# crystals.net
KiCad netlist of a schematic drawn in Altium Designer
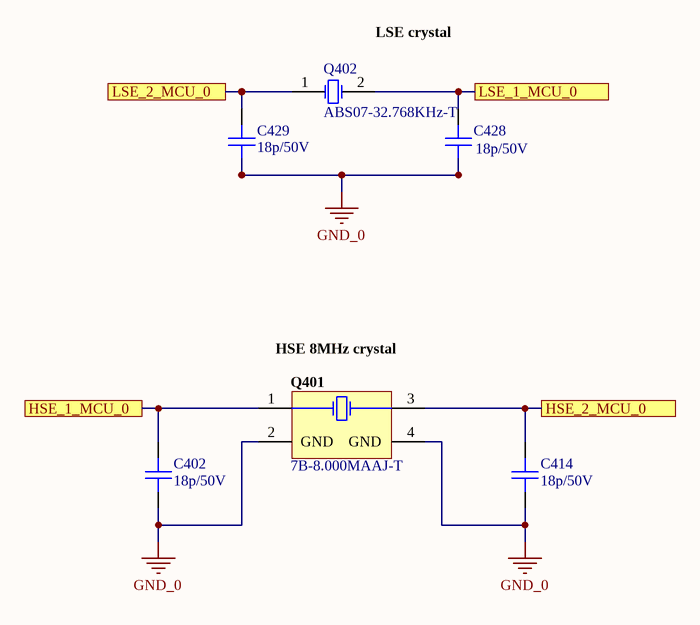
[diagram p0: crystals.SchDoc]

(export (version "E")
  (design (tool "Eeschema 10.0.6"))
  (components
    (comp (ref "C402")
      (value "18p/50V")
      (footprint "CAPC1608X08N")
      (description "MLCC")
      (fields (field (name "PART NUMBER") "gen_C_ceramic_18p_50V_C0G_0603"))
      (libsource (lib "OE750") (part "C"))
    )
    (comp (ref "C414")
      (value "18p/50V")
      (footprint "CAPC1608X08N")
      (description "MLCC")
      (fields (field (name "PART NUMBER") "gen_C_ceramic_18p_50V_C0G_0603"))
      (libsource (lib "OE750") (part "C"))
    )
    (comp (ref "C428")
      (value "18p/50V")
      (footprint "CAPC1608X08N")
      (description "MLCC")
      (fields (field (name "PART NUMBER") "gen_C_ceramic_18p_50V_C0G_0603"))
      (libsource (lib "OE750") (part "C"))
    )
    (comp (ref "C429")
      (value "18p/50V")
      (footprint "CAPC1608X08N")
      (description "MLCC")
      (fields (field (name "PART NUMBER") "gen_C_ceramic_18p_50V_C0G_0603"))
      (libsource (lib "OE750") (part "C"))
    )
    (comp (ref "Q401")
      (value "7B-8.000MAAJ-T")
      (footprint "TXC-7B-4_V")
      (description "SMD Seam Sealing Crystal, 8 MHz, +/- 30 ppm, 18 pF, -10 to 70 degC, 4-Pin SMD, RoHS, Tape and Reel")
      (fields (field (name "TOLERANCE") "1%"))
      (libsource (lib "Altium Content Vault") (part "XTAL-1-3-4"))
    )
    (comp (ref "Q402")
      (value "ABS07-32.768KHz-T")
      (footprint "ABRA-ABS07-2_V")
      (description "Crystal, 32.768 kHz, 12.5 pF, -40 to 85 degC, SMD Low Profile 3.2 x 1.5 x 0.9 mm, Tape and Reel")
      (fields (field (name "MANUFACTURER") "Abracon"))
      (libsource (lib "Altium Content Vault") (part "ABRA-ABS07-2"))
    )
  )
  (nets
    (net (code "1") (name "/HSE_1_MCU_0") (class "Default")
      (node (ref "C402") (pin "2") (pinfunction "2_2") (pintype "passive"))
      (node (ref "Q401") (pin "1") (pinfunction "X1_1") (pintype "passive"))
    )
    (net (code "2") (name "/HSE_2_MCU_0") (class "Default")
      (node (ref "C414") (pin "1") (pinfunction "1_1") (pintype "passive"))
      (node (ref "Q401") (pin "3") (pinfunction "X2_3") (pintype "passive"))
    )
    (net (code "3") (name "/LSE_1_MCU_0") (class "Default")
      (node (ref "C428") (pin "2") (pinfunction "2_2") (pintype "passive"))
      (node (ref "Q402") (pin "2") (pinfunction "X2_2") (pintype "passive"))
    )
    (net (code "4") (name "/LSE_2_MCU_0") (class "Default")
      (node (ref "C429") (pin "1") (pinfunction "1_1") (pintype "passive"))
      (node (ref "Q402") (pin "1") (pinfunction "X1_1") (pintype "passive"))
    )
    (net (code "5") (name "GND_0") (class "Default")
      (node (ref "C402") (pin "1") (pinfunction "1_1") (pintype "passive"))
      (node (ref "C414") (pin "2") (pinfunction "2_2") (pintype "passive"))
      (node (ref "C428") (pin "1") (pinfunction "1_1") (pintype "passive"))
      (node (ref "C429") (pin "2") (pinfunction "2_2") (pintype "passive"))
      (node (ref "Q401") (pin "2") (pinfunction "GND_2") (pintype "power_in"))
      (node (ref "Q401") (pin "4") (pinfunction "GND_4") (pintype "power_in"))
    )
  )
)
